# PalAdapter.net
KiCad netlist of a schematic drawn in EAGLE
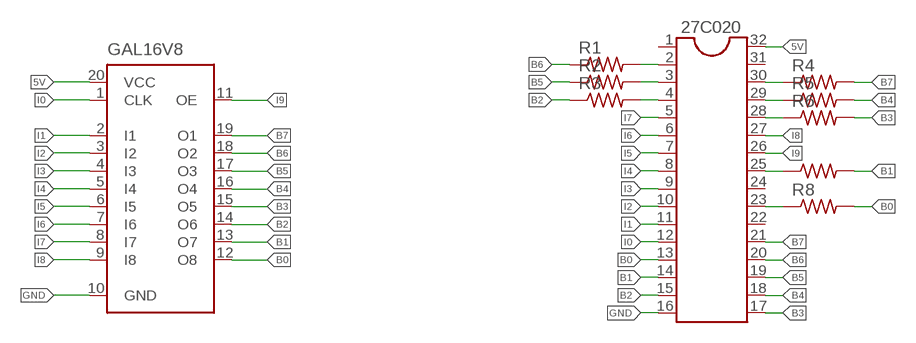
[diagram p0: schematic, sheet 1]

(export (version "E")
  (design (tool "Eeschema 10.0.6"))
  (components
    (comp (ref "27C020")
      (value "DIL32")
      (footprint "eagle-import:DIL32")
      (libsource (lib "eagle-import") (part "DIL32"))
    )
    (comp (ref "GAL16V8")
      (value "ATF16V8BP3")
      (footprint "eagle-import:DIL20")
      (fields (field (name "MPN") "ATF16V8CZ-15PU"))
      (libsource (lib "eagle-import") (part "ATF16V8BP3"))
    )
    (comp (ref "R1")
      (value "R-US_0204/7")
      (footprint "eagle-import:0204_7")
      (libsource (lib "eagle-import") (part "R-US_0204/7"))
    )
    (comp (ref "R2")
      (value "R-US_0204/7")
      (footprint "eagle-import:0204_7")
      (libsource (lib "eagle-import") (part "R-US_0204/7"))
    )
    (comp (ref "R3")
      (value "R-US_0204/7")
      (footprint "eagle-import:0204_7")
      (libsource (lib "eagle-import") (part "R-US_0204/7"))
    )
    (comp (ref "R4")
      (value "R-US_0204/7")
      (footprint "eagle-import:0204_7")
      (libsource (lib "eagle-import") (part "R-US_0204/7"))
    )
    (comp (ref "R5")
      (value "R-US_0204/7")
      (footprint "eagle-import:0204_7")
      (libsource (lib "eagle-import") (part "R-US_0204/7"))
    )
    (comp (ref "R6")
      (value "R-US_0204/7")
      (footprint "eagle-import:0204_7")
      (libsource (lib "eagle-import") (part "R-US_0204/7"))
    )
    (comp (ref "R7")
      (value "R-US_0204/7")
      (footprint "eagle-import:0204_7")
      (libsource (lib "eagle-import") (part "R-US_0204/7"))
    )
    (comp (ref "R8")
      (value "R-US_0204/7")
      (footprint "eagle-import:0204_7")
      (libsource (lib "eagle-import") (part "R-US_0204/7"))
    )
  )
  (nets
    (net (code "1") (name "5V") (class "Default")
      (node (ref "27C020") (pin "32") (pinfunction "32_32") (pintype "passive"))
      (node (ref "GAL16V8") (pin "20") (pinfunction "VCC_20") (pintype "power_in"))
    )
    (net (code "2") (name "B0") (class "Default")
      (node (ref "27C020") (pin "13") (pinfunction "13_13") (pintype "passive"))
      (node (ref "GAL16V8") (pin "12") (pinfunction "O8_12") (pintype "output"))
      (node (ref "R8") (pin "2") (pinfunction "2_2") (pintype "passive"))
    )
    (net (code "3") (name "B1") (class "Default")
      (node (ref "27C020") (pin "14") (pinfunction "14_14") (pintype "passive"))
      (node (ref "GAL16V8") (pin "13") (pinfunction "O7_13") (pintype "output"))
      (node (ref "R7") (pin "2") (pinfunction "2_2") (pintype "passive"))
    )
    (net (code "4") (name "B2") (class "Default")
      (node (ref "27C020") (pin "15") (pinfunction "15_15") (pintype "passive"))
      (node (ref "GAL16V8") (pin "14") (pinfunction "O6_14") (pintype "output"))
      (node (ref "R3") (pin "1") (pinfunction "1_1") (pintype "passive"))
    )
    (net (code "5") (name "B3") (class "Default")
      (node (ref "27C020") (pin "17") (pinfunction "17_17") (pintype "passive"))
      (node (ref "GAL16V8") (pin "15") (pinfunction "O5_15") (pintype "output"))
      (node (ref "R6") (pin "2") (pinfunction "2_2") (pintype "passive"))
    )
    (net (code "6") (name "B4") (class "Default")
      (node (ref "27C020") (pin "18") (pinfunction "18_18") (pintype "passive"))
      (node (ref "GAL16V8") (pin "16") (pinfunction "O4_16") (pintype "output"))
      (node (ref "R5") (pin "2") (pinfunction "2_2") (pintype "passive"))
    )
    (net (code "7") (name "B5") (class "Default")
      (node (ref "27C020") (pin "19") (pinfunction "19_19") (pintype "passive"))
      (node (ref "GAL16V8") (pin "17") (pinfunction "O3_17") (pintype "output"))
      (node (ref "R2") (pin "1") (pinfunction "1_1") (pintype "passive"))
    )
    (net (code "8") (name "B6") (class "Default")
      (node (ref "27C020") (pin "20") (pinfunction "20_20") (pintype "passive"))
      (node (ref "GAL16V8") (pin "18") (pinfunction "O2_18") (pintype "output"))
      (node (ref "R1") (pin "1") (pinfunction "1_1") (pintype "passive"))
    )
    (net (code "9") (name "B7") (class "Default")
      (node (ref "27C020") (pin "21") (pinfunction "21_21") (pintype "passive"))
      (node (ref "GAL16V8") (pin "19") (pinfunction "O1_19") (pintype "output"))
      (node (ref "R4") (pin "2") (pinfunction "2_2") (pintype "passive"))
    )
    (net (code "10") (name "GND") (class "Default")
      (node (ref "27C020") (pin "16") (pinfunction "16_16") (pintype "passive"))
      (node (ref "GAL16V8") (pin "10") (pinfunction "GND_10") (pintype "power_in"))
    )
    (net (code "11") (name "I0") (class "Default")
      (node (ref "27C020") (pin "12") (pinfunction "12_12") (pintype "passive"))
      (node (ref "GAL16V8") (pin "1") (pinfunction "CLK_1") (pintype "input"))
    )
    (net (code "12") (name "I1") (class "Default")
      (node (ref "27C020") (pin "11") (pinfunction "11_11") (pintype "passive"))
      (node (ref "GAL16V8") (pin "2") (pinfunction "I1_2") (pintype "input"))
    )
    (net (code "13") (name "I2") (class "Default")
      (node (ref "27C020") (pin "10") (pinfunction "10_10") (pintype "passive"))
      (node (ref "GAL16V8") (pin "3") (pinfunction "I2_3") (pintype "input"))
    )
    (net (code "14") (name "I3") (class "Default")
      (node (ref "27C020") (pin "9") (pinfunction "9_9") (pintype "passive"))
      (node (ref "GAL16V8") (pin "4") (pinfunction "I3_4") (pintype "input"))
    )
    (net (code "15") (name "I4") (class "Default")
      (node (ref "27C020") (pin "8") (pinfunction "8_8") (pintype "passive"))
      (node (ref "GAL16V8") (pin "5") (pinfunction "I4_5") (pintype "input"))
    )
    (net (code "16") (name "I5") (class "Default")
      (node (ref "27C020") (pin "7") (pinfunction "7_7") (pintype "passive"))
      (node (ref "GAL16V8") (pin "6") (pinfunction "I5_6") (pintype "input"))
    )
    (net (code "17") (name "I6") (class "Default")
      (node (ref "27C020") (pin "6") (pinfunction "6_6") (pintype "passive"))
      (node (ref "GAL16V8") (pin "7") (pinfunction "I6_7") (pintype "input"))
    )
    (net (code "18") (name "I7") (class "Default")
      (node (ref "27C020") (pin "5") (pinfunction "5_5") (pintype "passive"))
      (node (ref "GAL16V8") (pin "8") (pinfunction "I7_8") (pintype "input"))
    )
    (net (code "19") (name "I8") (class "Default")
      (node (ref "27C020") (pin "27") (pinfunction "27_27") (pintype "passive"))
      (node (ref "GAL16V8") (pin "9") (pinfunction "I8_9") (pintype "input"))
    )
    (net (code "20") (name "I9") (class "Default")
      (node (ref "27C020") (pin "26") (pinfunction "26_26") (pintype "passive"))
      (node (ref "GAL16V8") (pin "11") (pinfunction "OE_11") (pintype "input"))
    )
    (net (code "21") (name "Net-(27C020-Pad2)") (class "Default")
      (node (ref "27C020") (pin "2") (pinfunction "2_2") (pintype "passive"))
      (node (ref "R1") (pin "2") (pinfunction "2_2") (pintype "passive"))
    )
    (net (code "22") (name "Net-(27C020-Pad3)") (class "Default")
      (node (ref "27C020") (pin "3") (pinfunction "3_3") (pintype "passive"))
      (node (ref "R2") (pin "2") (pinfunction "2_2") (pintype "passive"))
    )
    (net (code "23") (name "Net-(27C020-Pad4)") (class "Default")
      (node (ref "27C020") (pin "4") (pinfunction "4_4") (pintype "passive"))
      (node (ref "R3") (pin "2") (pinfunction "2_2") (pintype "passive"))
    )
    (net (code "24") (name "Net-(27C020-Pad23)") (class "Default")
      (node (ref "27C020") (pin "23") (pinfunction "23_23") (pintype "passive"))
      (node (ref "R8") (pin "1") (pinfunction "1_1") (pintype "passive"))
    )
    (net (code "25") (name "Net-(27C020-Pad25)") (class "Default")
      (node (ref "27C020") (pin "25") (pinfunction "25_25") (pintype "passive"))
      (node (ref "R7") (pin "1") (pinfunction "1_1") (pintype "passive"))
    )
    (net (code "26") (name "Net-(27C020-Pad28)") (class "Default")
      (node (ref "27C020") (pin "28") (pinfunction "28_28") (pintype "passive"))
      (node (ref "R6") (pin "1") (pinfunction "1_1") (pintype "passive"))
    )
    (net (code "27") (name "Net-(27C020-Pad29)") (class "Default")
      (node (ref "27C020") (pin "29") (pinfunction "29_29") (pintype "passive"))
      (node (ref "R5") (pin "1") (pinfunction "1_1") (pintype "passive"))
    )
    (net (code "28") (name "Net-(27C020-Pad30)") (class "Default")
      (node (ref "27C020") (pin "30") (pinfunction "30_30") (pintype "passive"))
      (node (ref "R4") (pin "1") (pinfunction "1_1") (pintype "passive"))
    )
    (net (code "29") (name "unconnected-(27C020-Pad1)") (class "Default")
      (node (ref "27C020") (pin "1") (pinfunction "1_1") (pintype "passive"))
    )
    (net (code "30") (name "unconnected-(27C020-Pad22)") (class "Default")
      (node (ref "27C020") (pin "22") (pinfunction "22_22") (pintype "passive"))
    )
    (net (code "31") (name "unconnected-(27C020-Pad24)") (class "Default")
      (node (ref "27C020") (pin "24") (pinfunction "24_24") (pintype "passive"))
    )
    (net (code "32") (name "unconnected-(27C020-Pad31)") (class "Default")
      (node (ref "27C020") (pin "31") (pinfunction "31_31") (pintype "passive"))
    )
  )
)
